# TRV_CC110x_V0_3.net
KiCad netlist of a schematic drawn in EAGLE
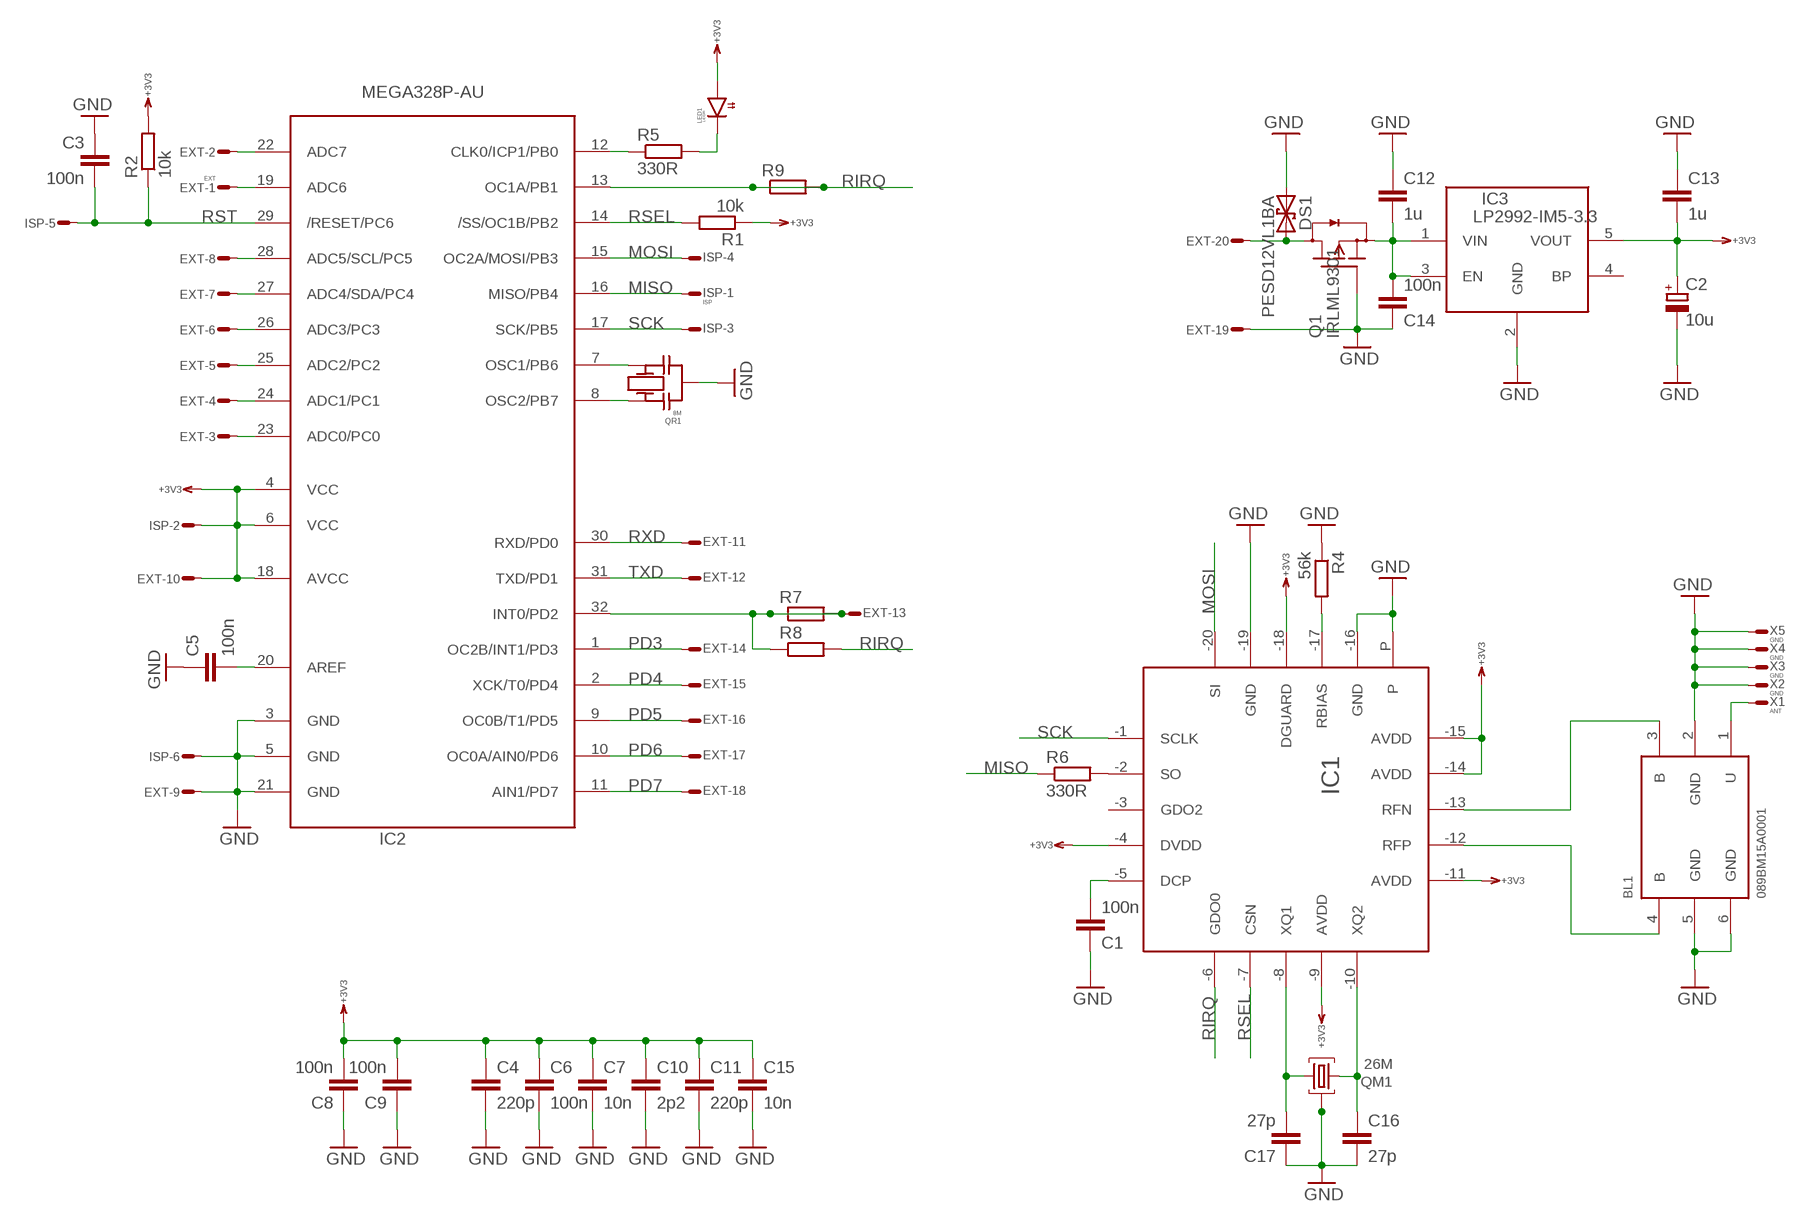
[diagram p0: schematic, sheet 1]

(export (version "E")
  (design (tool "Eeschema 10.0.6"))
  (components
    (comp (ref "BL1")
      (value "089BM15A0001")
      (footprint "eagle-import:BL")
      (libsource (lib "eagle-import") (part "BL"))
    )
    (comp (ref "C1")
      (value "100n")
      (footprint "eagle-import:0402")
      (libsource (lib "eagle-import") (part "C0402"))
    )
    (comp (ref "C2")
      (value "10u")
      (footprint "eagle-import:SMC_B")
      (libsource (lib "eagle-import") (part "C_POLSMCB"))
    )
    (comp (ref "C3")
      (value "100n")
      (footprint "eagle-import:0603")
      (libsource (lib "eagle-import") (part "C0603"))
    )
    (comp (ref "C4")
      (value "220p")
      (footprint "eagle-import:0402")
      (libsource (lib "eagle-import") (part "C0402"))
    )
    (comp (ref "C5")
      (value "100n")
      (footprint "eagle-import:0603")
      (libsource (lib "eagle-import") (part "C0603"))
    )
    (comp (ref "C6")
      (value "100n")
      (footprint "eagle-import:0402")
      (libsource (lib "eagle-import") (part "C0402"))
    )
    (comp (ref "C7")
      (value "10n")
      (footprint "eagle-import:0402")
      (libsource (lib "eagle-import") (part "C0402"))
    )
    (comp (ref "C8")
      (value "100n")
      (footprint "eagle-import:0603")
      (libsource (lib "eagle-import") (part "C0603"))
    )
    (comp (ref "C9")
      (value "100n")
      (footprint "eagle-import:0603")
      (libsource (lib "eagle-import") (part "C0603"))
    )
    (comp (ref "C10")
      (value "2p2")
      (footprint "eagle-import:0402")
      (libsource (lib "eagle-import") (part "C0402"))
    )
    (comp (ref "C11")
      (value "220p")
      (footprint "eagle-import:0402")
      (libsource (lib "eagle-import") (part "C0402"))
    )
    (comp (ref "C12")
      (value "1u")
      (footprint "eagle-import:0603")
      (libsource (lib "eagle-import") (part "C0603"))
    )
    (comp (ref "C13")
      (value "1u")
      (footprint "eagle-import:0603")
      (libsource (lib "eagle-import") (part "C0603"))
    )
    (comp (ref "C14")
      (value "100n")
      (footprint "eagle-import:0603")
      (libsource (lib "eagle-import") (part "C0603"))
    )
    (comp (ref "C15")
      (value "10n")
      (footprint "eagle-import:0402")
      (libsource (lib "eagle-import") (part "C0402"))
    )
    (comp (ref "C16")
      (value "27p")
      (footprint "eagle-import:0402")
      (libsource (lib "eagle-import") (part "C0402"))
    )
    (comp (ref "C17")
      (value "27p")
      (footprint "eagle-import:0402")
      (libsource (lib "eagle-import") (part "C0402"))
    )
    (comp (ref "DS1")
      (value "PESD12VL1BA")
      (footprint "eagle-import:SOD323")
      (libsource (lib "eagle-import") (part "TVS-U323"))
    )
    (comp (ref "EXT")
      (value "EXT")
      (footprint "eagle-import:ML20S")
      (libsource (lib "eagle-import") (part "ML20?ES"))
    )
    (comp (ref "IC1")
      (value "CC110L")
      (footprint "eagle-import:VQFN20")
      (libsource (lib "eagle-import") (part "CC110L"))
    )
    (comp (ref "IC2")
      (value "MEGA328P-AU")
      (footprint "eagle-import:TQFP32-08")
      (libsource (lib "eagle-import") (part "MEGA168PA"))
    )
    (comp (ref "IC3")
      (value "LP2992-IM5-3.3")
      (footprint "eagle-import:SOT23-5")
      (libsource (lib "eagle-import") (part "LDO"))
    )
    (comp (ref "ISP")
      (value "ISP")
      (footprint "eagle-import:ML6S")
      (libsource (lib "eagle-import") (part "ML6ES"))
    )
    (comp (ref "LED1")
      (value "LEDR")
      (footprint "eagle-import:T1-3_4")
      (libsource (lib "eagle-import") (part "LEDT134"))
    )
    (comp (ref "Q1")
      (value "IRLML9301")
      (footprint "eagle-import:SOT23")
      (libsource (lib "eagle-import") (part "FET-PDSOT23"))
    )
    (comp (ref "QM1")
      (value "26M")
      (footprint "eagle-import:SMD_4P_3.2X2.5")
      (libsource (lib "eagle-import") (part "QM3.2X2.5"))
    )
    (comp (ref "QR1")
      (value "8M")
      (footprint "eagle-import:CR")
      (libsource (lib "eagle-import") (part "QRCR"))
    )
    (comp (ref "R1")
      (value "10k")
      (footprint "eagle-import:0402")
      (libsource (lib "eagle-import") (part "R0402"))
    )
    (comp (ref "R2")
      (value "10k")
      (footprint "eagle-import:0603")
      (libsource (lib "eagle-import") (part "R0603"))
    )
    (comp (ref "R4")
      (value "56k")
      (footprint "eagle-import:0402")
      (libsource (lib "eagle-import") (part "R0402"))
    )
    (comp (ref "R5")
      (value "330R")
      (footprint "eagle-import:0402")
      (libsource (lib "eagle-import") (part "R0402"))
    )
    (comp (ref "R6")
      (value "330R")
      (footprint "eagle-import:0402")
      (libsource (lib "eagle-import") (part "R0402"))
    )
    (comp (ref "R7")
      (value "R0402")
      (footprint "eagle-import:0402")
      (libsource (lib "eagle-import") (part "R0402"))
    )
    (comp (ref "R8")
      (value "R0402")
      (footprint "eagle-import:0402")
      (libsource (lib "eagle-import") (part "R0402"))
    )
    (comp (ref "R9")
      (value "R0402")
      (footprint "eagle-import:0402")
      (libsource (lib "eagle-import") (part "R0402"))
    )
    (comp (ref "X1")
      (value "ANT")
      (footprint "eagle-import:S2.54_1.27")
      (libsource (lib "eagle-import") (part "WIREPADS2.54/1.27"))
    )
    (comp (ref "X2")
      (value "GND")
      (footprint "eagle-import:S2.54_1.27")
      (libsource (lib "eagle-import") (part "WIREPADS2.54/1.27"))
    )
    (comp (ref "X3")
      (value "GND")
      (footprint "eagle-import:S2.54_1.27")
      (libsource (lib "eagle-import") (part "WIREPADS2.54/1.27"))
    )
    (comp (ref "X4")
      (value "GND")
      (footprint "eagle-import:S2.54_1.27")
      (libsource (lib "eagle-import") (part "WIREPADS2.54/1.27"))
    )
    (comp (ref "X5")
      (value "GND")
      (footprint "eagle-import:S2.54_1.27")
      (libsource (lib "eagle-import") (part "WIREPADS2.54/1.27"))
    )
  )
  (nets
    (net (code "1") (name "+3V3") (class "Default")
      (node (ref "C10") (pin "1") (pinfunction "1_1") (pintype "passive"))
      (node (ref "C11") (pin "1") (pinfunction "1_1") (pintype "passive"))
      (node (ref "C13") (pin "2") (pinfunction "2_2") (pintype "passive"))
      (node (ref "C15") (pin "1") (pinfunction "1_1") (pintype "passive"))
      (node (ref "C2") (pin "+") (pinfunction "+_+") (pintype "passive"))
      (node (ref "C4") (pin "1") (pinfunction "1_1") (pintype "passive"))
      (node (ref "C6") (pin "1") (pinfunction "1_1") (pintype "passive"))
      (node (ref "C7") (pin "1") (pinfunction "1_1") (pintype "passive"))
      (node (ref "C8") (pin "2") (pinfunction "2_2") (pintype "passive"))
      (node (ref "C9") (pin "2") (pinfunction "2_2") (pintype "passive"))
      (node (ref "EXT") (pin "10") (pinfunction "S_10") (pintype "passive"))
      (node (ref "IC1") (pin "-11") (pinfunction "AVDD_-11") (pintype "bidirectional"))
      (node (ref "IC1") (pin "-14") (pinfunction "AVDD_-14") (pintype "bidirectional"))
      (node (ref "IC1") (pin "-15") (pinfunction "AVDD_-15") (pintype "bidirectional"))
      (node (ref "IC1") (pin "-18") (pinfunction "DGUARD_-18") (pintype "bidirectional"))
      (node (ref "IC1") (pin "-4") (pinfunction "DVDD_-4") (pintype "bidirectional"))
      (node (ref "IC1") (pin "-9") (pinfunction "AVDD_-9") (pintype "bidirectional"))
      (node (ref "IC2") (pin "18") (pinfunction "AVCC_18") (pintype "bidirectional"))
      (node (ref "IC2") (pin "4") (pinfunction "VCC_4") (pintype "bidirectional"))
      (node (ref "IC2") (pin "6") (pinfunction "VCC_6") (pintype "bidirectional"))
      (node (ref "IC3") (pin "5") (pinfunction "VOUT_5") (pintype "bidirectional"))
      (node (ref "ISP") (pin "2") (pinfunction "S_2") (pintype "passive"))
      (node (ref "LED1") (pin "A") (pinfunction "A_A") (pintype "bidirectional"))
      (node (ref "R1") (pin "1") (pinfunction "1_1") (pintype "passive"))
      (node (ref "R2") (pin "2") (pinfunction "2_2") (pintype "passive"))
    )
    (net (code "2") (name "/MISO") (class "Default")
      (node (ref "IC2") (pin "16") (pinfunction "MISO/PB4_16") (pintype "bidirectional"))
      (node (ref "ISP") (pin "1") (pinfunction "S_1") (pintype "passive"))
      (node (ref "R6") (pin "1") (pinfunction "1_1") (pintype "passive"))
    )
    (net (code "3") (name "/MOSI") (class "Default")
      (node (ref "IC1") (pin "-20") (pinfunction "SI_-20") (pintype "input"))
      (node (ref "IC2") (pin "15") (pinfunction "OC2A/MOSI/PB3_15") (pintype "bidirectional"))
      (node (ref "ISP") (pin "4") (pinfunction "S_4") (pintype "passive"))
    )
    (net (code "4") (name "/PD3") (class "Default")
      (node (ref "EXT") (pin "14") (pinfunction "S_14") (pintype "passive"))
      (node (ref "IC2") (pin "1") (pinfunction "OC2B/INT1/PD3_1") (pintype "bidirectional"))
    )
    (net (code "5") (name "/PD4") (class "Default")
      (node (ref "EXT") (pin "15") (pinfunction "S_15") (pintype "passive"))
      (node (ref "IC2") (pin "2") (pinfunction "XCK/T0/PD4_2") (pintype "bidirectional"))
    )
    (net (code "6") (name "/PD5") (class "Default")
      (node (ref "EXT") (pin "16") (pinfunction "S_16") (pintype "passive"))
      (node (ref "IC2") (pin "9") (pinfunction "OC0B/T1/PD5_9") (pintype "bidirectional"))
    )
    (net (code "7") (name "/PD6") (class "Default")
      (node (ref "EXT") (pin "17") (pinfunction "S_17") (pintype "passive"))
      (node (ref "IC2") (pin "10") (pinfunction "OC0A/AIN0/PD6_10") (pintype "bidirectional"))
    )
    (net (code "8") (name "/PD7") (class "Default")
      (node (ref "EXT") (pin "18") (pinfunction "S_18") (pintype "passive"))
      (node (ref "IC2") (pin "11") (pinfunction "AIN1/PD7_11") (pintype "bidirectional"))
    )
    (net (code "9") (name "/RIRQ") (class "Default")
      (node (ref "IC1") (pin "-6") (pinfunction "GDO0_-6") (pintype "bidirectional"))
      (node (ref "IC2") (pin "13") (pinfunction "OC1A/PB1_13") (pintype "bidirectional"))
      (node (ref "R8") (pin "2") (pinfunction "2_2") (pintype "passive"))
      (node (ref "R9") (pin "1") (pinfunction "1_1") (pintype "passive"))
      (node (ref "R9") (pin "2") (pinfunction "2_2") (pintype "passive"))
    )
    (net (code "10") (name "/RSEL") (class "Default")
      (node (ref "IC1") (pin "-7") (pinfunction "CSN_-7") (pintype "input"))
      (node (ref "IC2") (pin "14") (pinfunction "/SS/OC1B/PB2_14") (pintype "bidirectional"))
      (node (ref "R1") (pin "2") (pinfunction "2_2") (pintype "passive"))
    )
    (net (code "11") (name "/RST") (class "Default")
      (node (ref "C3") (pin "2") (pinfunction "2_2") (pintype "passive"))
      (node (ref "IC2") (pin "29") (pinfunction "/RESET/PC6_29") (pintype "bidirectional"))
      (node (ref "ISP") (pin "5") (pinfunction "S_5") (pintype "passive"))
      (node (ref "R2") (pin "1") (pinfunction "1_1") (pintype "passive"))
    )
    (net (code "12") (name "/RXD") (class "Default")
      (node (ref "EXT") (pin "11") (pinfunction "S_11") (pintype "passive"))
      (node (ref "IC2") (pin "30") (pinfunction "RXD/PD0_30") (pintype "bidirectional"))
    )
    (net (code "13") (name "/SCK") (class "Default")
      (node (ref "IC1") (pin "-1") (pinfunction "SCLK_-1") (pintype "input"))
      (node (ref "IC2") (pin "17") (pinfunction "SCK/PB5_17") (pintype "bidirectional"))
      (node (ref "ISP") (pin "3") (pinfunction "S_3") (pintype "passive"))
    )
    (net (code "14") (name "/TXD") (class "Default")
      (node (ref "EXT") (pin "12") (pinfunction "S_12") (pintype "passive"))
      (node (ref "IC2") (pin "31") (pinfunction "TXD/PD1_31") (pintype "bidirectional"))
    )
    (net (code "15") (name "GND") (class "Default")
      (node (ref "BL1") (pin "2") (pinfunction "GND_2") (pintype "bidirectional"))
      (node (ref "BL1") (pin "5") (pinfunction "GND_5") (pintype "bidirectional"))
      (node (ref "BL1") (pin "6") (pinfunction "GND_6") (pintype "bidirectional"))
      (node (ref "C1") (pin "1") (pinfunction "1_1") (pintype "passive"))
      (node (ref "C10") (pin "2") (pinfunction "2_2") (pintype "passive"))
      (node (ref "C11") (pin "2") (pinfunction "2_2") (pintype "passive"))
      (node (ref "C12") (pin "1") (pinfunction "1_1") (pintype "passive"))
      (node (ref "C13") (pin "1") (pinfunction "1_1") (pintype "passive"))
      (node (ref "C14") (pin "1") (pinfunction "1_1") (pintype "passive"))
      (node (ref "C15") (pin "2") (pinfunction "2_2") (pintype "passive"))
      (node (ref "C16") (pin "2") (pinfunction "2_2") (pintype "passive"))
      (node (ref "C17") (pin "1") (pinfunction "1_1") (pintype "passive"))
      (node (ref "C2") (pin "-") (pinfunction "-_-") (pintype "passive"))
      (node (ref "C3") (pin "1") (pinfunction "1_1") (pintype "passive"))
      (node (ref "C4") (pin "2") (pinfunction "2_2") (pintype "passive"))
      (node (ref "C5") (pin "1") (pinfunction "1_1") (pintype "passive"))
      (node (ref "C6") (pin "2") (pinfunction "2_2") (pintype "passive"))
      (node (ref "C7") (pin "2") (pinfunction "2_2") (pintype "passive"))
      (node (ref "C8") (pin "1") (pinfunction "1_1") (pintype "passive"))
      (node (ref "C9") (pin "1") (pinfunction "1_1") (pintype "passive"))
      (node (ref "DS1") (pin "A") (pinfunction "1_A") (pintype "passive"))
      (node (ref "EXT") (pin "19") (pinfunction "S_19") (pintype "passive"))
      (node (ref "EXT") (pin "9") (pinfunction "S_9") (pintype "passive"))
      (node (ref "IC1") (pin "-16") (pinfunction "GND_-16") (pintype "bidirectional"))
      (node (ref "IC1") (pin "-19") (pinfunction "GND_-19") (pintype "bidirectional"))
      (node (ref "IC1") (pin "P") (pinfunction "P_P") (pintype "bidirectional"))
      (node (ref "IC2") (pin "21") (pinfunction "GND_21") (pintype "bidirectional"))
      (node (ref "IC2") (pin "3") (pinfunction "GND_3") (pintype "bidirectional"))
      (node (ref "IC2") (pin "5") (pinfunction "GND_5") (pintype "bidirectional"))
      (node (ref "IC3") (pin "2") (pinfunction "GND_2") (pintype "bidirectional"))
      (node (ref "ISP") (pin "6") (pinfunction "S_6") (pintype "passive"))
      (node (ref "Q1") (pin "1") (pinfunction "G_1") (pintype "passive"))
      (node (ref "QM1") (pin "2") (pinfunction "M1_2") (pintype "passive"))
      (node (ref "QM1") (pin "4") (pinfunction "M2_4") (pintype "passive"))
      (node (ref "QR1") (pin "M") (pinfunction "M_M") (pintype "passive"))
      (node (ref "R4") (pin "1") (pinfunction "1_1") (pintype "passive"))
      (node (ref "X2") (pin "1") (pinfunction "S_1") (pintype "passive"))
      (node (ref "X3") (pin "1") (pinfunction "S_1") (pintype "passive"))
      (node (ref "X4") (pin "1") (pinfunction "S_1") (pintype "passive"))
      (node (ref "X5") (pin "1") (pinfunction "S_1") (pintype "passive"))
    )
    (net (code "16") (name "Net-(BL1-U)") (class "Default")
      (node (ref "BL1") (pin "1") (pinfunction "U_1") (pintype "bidirectional"))
      (node (ref "X1") (pin "1") (pinfunction "S_1") (pintype "passive"))
    )
    (net (code "17") (name "Net-(DS1-2)") (class "Default")
      (node (ref "DS1") (pin "C") (pinfunction "2_C") (pintype "passive"))
      (node (ref "EXT") (pin "20") (pinfunction "S_20") (pintype "passive"))
      (node (ref "Q1") (pin "3") (pinfunction "D_3") (pintype "passive"))
    )
    (net (code "18") (name "Net-(EXTA-S)") (class "Default")
      (node (ref "EXT") (pin "1") (pinfunction "S_1") (pintype "passive"))
      (node (ref "IC2") (pin "19") (pinfunction "ADC6_19") (pintype "bidirectional"))
    )
    (net (code "19") (name "Net-(EXTE-S)") (class "Default")
      (node (ref "EXT") (pin "13") (pinfunction "S_13") (pintype "passive"))
      (node (ref "IC2") (pin "32") (pinfunction "INT0/PD2_32") (pintype "bidirectional"))
      (node (ref "R7") (pin "1") (pinfunction "1_1") (pintype "passive"))
      (node (ref "R7") (pin "2") (pinfunction "2_2") (pintype "passive"))
      (node (ref "R8") (pin "1") (pinfunction "1_1") (pintype "passive"))
    )
    (net (code "20") (name "Net-(EXTL-S)") (class "Default")
      (node (ref "EXT") (pin "2") (pinfunction "S_2") (pintype "passive"))
      (node (ref "IC2") (pin "22") (pinfunction "ADC7_22") (pintype "bidirectional"))
    )
    (net (code "21") (name "Net-(EXTN-S)") (class "Default")
      (node (ref "EXT") (pin "3") (pinfunction "S_3") (pintype "passive"))
      (node (ref "IC2") (pin "23") (pinfunction "ADC0/PC0_23") (pintype "bidirectional"))
    )
    (net (code "22") (name "Net-(EXTO-S)") (class "Default")
      (node (ref "EXT") (pin "4") (pinfunction "S_4") (pintype "passive"))
      (node (ref "IC2") (pin "24") (pinfunction "ADC1/PC1_24") (pintype "bidirectional"))
    )
    (net (code "23") (name "Net-(EXTP-S)") (class "Default")
      (node (ref "EXT") (pin "5") (pinfunction "S_5") (pintype "passive"))
      (node (ref "IC2") (pin "25") (pinfunction "ADC2/PC2_25") (pintype "bidirectional"))
    )
    (net (code "24") (name "Net-(EXTQ-S)") (class "Default")
      (node (ref "EXT") (pin "6") (pinfunction "S_6") (pintype "passive"))
      (node (ref "IC2") (pin "26") (pinfunction "ADC3/PC3_26") (pintype "bidirectional"))
    )
    (net (code "25") (name "Net-(EXTR-S)") (class "Default")
      (node (ref "EXT") (pin "7") (pinfunction "S_7") (pintype "passive"))
      (node (ref "IC2") (pin "27") (pinfunction "ADC4/SDA/PC4_27") (pintype "bidirectional"))
    )
    (net (code "26") (name "Net-(EXTS-S)") (class "Default")
      (node (ref "EXT") (pin "8") (pinfunction "S_8") (pintype "passive"))
      (node (ref "IC2") (pin "28") (pinfunction "ADC5/SCL/PC5_28") (pintype "bidirectional"))
    )
    (net (code "27") (name "Net-(IC1-DCP)") (class "Default")
      (node (ref "C1") (pin "2") (pinfunction "2_2") (pintype "passive"))
      (node (ref "IC1") (pin "-5") (pinfunction "DCP_-5") (pintype "bidirectional"))
    )
    (net (code "28") (name "Net-(IC1-RBIAS)") (class "Default")
      (node (ref "IC1") (pin "-17") (pinfunction "RBIAS_-17") (pintype "bidirectional"))
      (node (ref "R4") (pin "2") (pinfunction "2_2") (pintype "passive"))
    )
    (net (code "29") (name "Net-(IC1-RFN)") (class "Default")
      (node (ref "BL1") (pin "3") (pinfunction "B_3") (pintype "bidirectional"))
      (node (ref "IC1") (pin "-13") (pinfunction "RFN_-13") (pintype "bidirectional"))
    )
    (net (code "30") (name "Net-(IC1-RFP)") (class "Default")
      (node (ref "BL1") (pin "4") (pinfunction "B_4") (pintype "bidirectional"))
      (node (ref "IC1") (pin "-12") (pinfunction "RFP_-12") (pintype "bidirectional"))
    )
    (net (code "31") (name "Net-(IC1-SO)") (class "Default")
      (node (ref "IC1") (pin "-2") (pinfunction "SO_-2") (pintype "output"))
      (node (ref "R6") (pin "2") (pinfunction "2_2") (pintype "passive"))
    )
    (net (code "32") (name "Net-(IC1-XQ1)") (class "Default")
      (node (ref "C17") (pin "2") (pinfunction "2_2") (pintype "passive"))
      (node (ref "IC1") (pin "-8") (pinfunction "XQ1_-8") (pintype "bidirectional"))
      (node (ref "QM1") (pin "3") (pinfunction "2_3") (pintype "passive"))
    )
    (net (code "33") (name "Net-(IC1-XQ2)") (class "Default")
      (node (ref "C16") (pin "1") (pinfunction "1_1") (pintype "passive"))
      (node (ref "IC1") (pin "-10") (pinfunction "XQ2_-10") (pintype "bidirectional"))
      (node (ref "QM1") (pin "1") (pinfunction "1_1") (pintype "passive"))
    )
    (net (code "34") (name "Net-(IC2-AREF)") (class "Default")
      (node (ref "C5") (pin "2") (pinfunction "2_2") (pintype "passive"))
      (node (ref "IC2") (pin "20") (pinfunction "AREF_20") (pintype "bidirectional"))
    )
    (net (code "35") (name "Net-(IC2-CLK0{slash}ICP1{slash}PB0)") (class "Default")
      (node (ref "IC2") (pin "12") (pinfunction "CLK0/ICP1/PB0_12") (pintype "bidirectional"))
      (node (ref "R5") (pin "1") (pinfunction "1_1") (pintype "passive"))
    )
    (net (code "36") (name "Net-(IC2-OSC1{slash}PB6)") (class "Default")
      (node (ref "IC2") (pin "7") (pinfunction "OSC1/PB6_7") (pintype "bidirectional"))
      (node (ref "QR1") (pin "2") (pinfunction "2_2") (pintype "passive"))
    )
    (net (code "37") (name "Net-(IC2-OSC2{slash}PB7)") (class "Default")
      (node (ref "IC2") (pin "8") (pinfunction "OSC2/PB7_8") (pintype "bidirectional"))
      (node (ref "QR1") (pin "1") (pinfunction "1_1") (pintype "passive"))
    )
    (net (code "38") (name "Net-(IC3-EN)") (class "Default")
      (node (ref "C12") (pin "2") (pinfunction "2_2") (pintype "passive"))
      (node (ref "C14") (pin "2") (pinfunction "2_2") (pintype "passive"))
      (node (ref "IC3") (pin "1") (pinfunction "VIN_1") (pintype "bidirectional"))
      (node (ref "IC3") (pin "3") (pinfunction "EN_3") (pintype "bidirectional"))
      (node (ref "Q1") (pin "2") (pinfunction "S_2") (pintype "passive"))
    )
    (net (code "39") (name "Net-(LED1-PadC)") (class "Default")
      (node (ref "LED1") (pin "C") (pinfunction "C_C") (pintype "bidirectional"))
      (node (ref "R5") (pin "2") (pinfunction "2_2") (pintype "passive"))
    )
    (net (code "40") (name "unconnected-(IC1-GDO2-Pad-3)") (class "Default")
      (node (ref "IC1") (pin "-3") (pinfunction "GDO2_-3") (pintype "output"))
    )
    (net (code "41") (name "unconnected-(IC3-BP-Pad4)") (class "Default")
      (node (ref "IC3") (pin "4") (pinfunction "BP_4") (pintype "bidirectional"))
    )
  )
)
